# Sheet1.net
KiCad netlist of a schematic drawn in Altium Designer
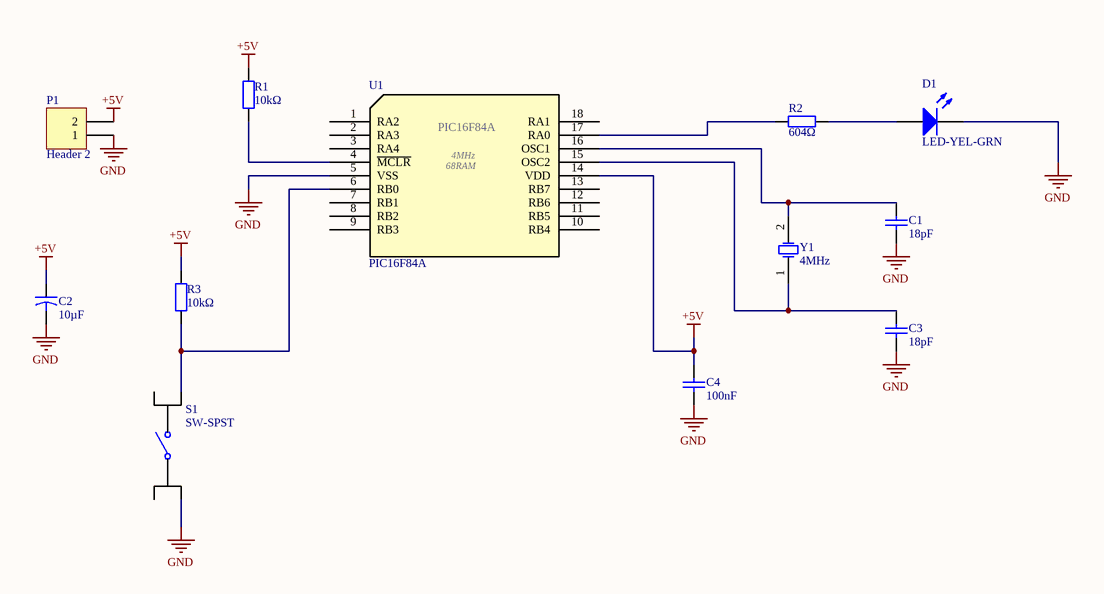
[diagram p0: Sheet1.SchDoc]

(export (version "E")
  (design (tool "Eeschema 10.0.6"))
  (components
    (comp (ref "C1")
      (value "18pF")
      (footprint "capacitor0603nopolar")
      (description "Capacitor")
      (fields (field (name "MANUFACTURER") "WALSIN") (field (name "VOLTAGE") "50V"))
      (libsource (lib "Schlib1") (part "Cap 18pF"))
    )
    (comp (ref "C2")
      (value "Cap 10uF")
      (footprint "cappolar_CM1H106M6L006VR")
      (description "Capacitor")
      (fields
        (field (name "CAPACITY") "10µF")
        (field (name "TOLERANCE") "±20%")
        (field (name "MANUFACTURER") "SAMWHA")
      )
      (libsource (lib "Schlib1") (part "Cap 10uF"))
    )
    (comp (ref "C3")
      (value "18pF")
      (footprint "capacitor0603nopolar")
      (description "Capacitor")
      (fields (field (name "MANUFACTURER") "WALSIN") (field (name "VOLTAGE") "50V"))
      (libsource (lib "Schlib1") (part "Cap 18pF"))
    )
    (comp (ref "C4")
      (value "100nF")
      (footprint "capacitor0603nopolar")
      (description "Capacitor")
      (fields (field (name "MANUFACTURER") "WALSIN") (field (name "VOLTAGE") "100V"))
      (libsource (lib "Schlib1") (part "Cap 100nF"))
    )
    (comp (ref "D1")
      (value "LED-YEL-GRN")
      (footprint "diode0603")
      (description "Typical INFRARED GaAs LED")
      (fields (field (name "MANUFACTURER") "EVERLIGHT") (field (name "VOLTAGE") "1,7...2,4V"))
      (libsource (lib "Schlib1") (part "LED-YEL-GRN"))
    )
    (comp (ref "P1")
      (value "Header 2")
      (footprint "header2,54")
      (description "Header, 2-Pin")
      (fields (field (name "MANUFACTURER") "TE CONNECTIVITY"))
      (libsource (lib "Schlib1") (part "Header 2"))
    )
    (comp (ref "R1")
      (value "10kΩ")
      (footprint "resistor0603")
      (description "Resistor")
      (fields (field (name "MANUFACTURER") "ROYAL OHM") (field (name "TOLERANCE") "±1%"))
      (libsource (lib "Schlib1") (part "Resistor 10Kohm"))
    )
    (comp (ref "R2")
      (value "604Ω")
      (footprint "resistor0603")
      (description "Resistor")
      (fields
        (field (name "MANUFACTURER") "WALSIN")
        (field (name "TOLERANCE") "±1%")
        (field (name "RESISTANCE") "604Ω")
      )
      (libsource (lib "Schlib1") (part "Resistor 604ohm"))
    )
    (comp (ref "R3")
      (value "10kΩ")
      (footprint "resistor0603")
      (description "Resistor")
      (fields (field (name "MANUFACTURER") "ROYAL OHM") (field (name "TOLERANCE") "±1%"))
      (libsource (lib "Schlib1") (part "Resistor 10Kohm"))
    )
    (comp (ref "S1")
      (value "SW-SPST")
      (footprint "switch")
      (description "Single-Pole, Single-Throw Switch")
      (fields (field (name "MANUFACTURER") "NKK SWITCHES"))
      (libsource (lib "Schlib1") (part "SW-SPST"))
    )
    (comp (ref "U1")
      (value "PIC16F84A")
      (footprint "DIP18")
      (description "Microchip")
      (fields (field (name "VOLTAGE") "4...5,5V DC") (field (name "MANUFACTURER") "MICROCHIP TECHNOLOGY"))
      (libsource (lib "Schlib1") (part "PIC16F84A"))
    )
    (comp (ref "Y1")
      (value "4MHz")
      (footprint "oscilator_XTAL003071")
      (description "Crystal Oscillator")
      (fields (field (name "MANUFACTURER") "IQD FREQUENCY PRODUCTS") (field (name "POWER") "0,5mW"))
      (libsource (lib "Schlib1") (part "Oscylator 4MHz"))
    )
  )
  (nets
    (net (code "1") (name "+5V") (class "Default")
      (node (ref "C2") (pin "1") (pinfunction "1_1") (pintype "passive"))
      (node (ref "C4") (pin "2") (pinfunction "2_2") (pintype "passive"))
      (node (ref "P1") (pin "2") (pinfunction "2_2") (pintype "passive"))
      (node (ref "R1") (pin "2") (pinfunction "2_2") (pintype "passive"))
      (node (ref "R3") (pin "2") (pinfunction "2_2") (pintype "passive"))
      (node (ref "U1") (pin "14") (pinfunction "VDD_14") (pintype "passive"))
    )
    (net (code "2") (name "GND") (class "Default")
      (node (ref "C1") (pin "1") (pinfunction "1_1") (pintype "passive"))
      (node (ref "C2") (pin "2") (pinfunction "2_2") (pintype "passive"))
      (node (ref "C3") (pin "1") (pinfunction "1_1") (pintype "passive"))
      (node (ref "C4") (pin "1") (pinfunction "1_1") (pintype "passive"))
      (node (ref "D1") (pin "2") (pinfunction "K_2") (pintype "passive"))
      (node (ref "P1") (pin "1") (pinfunction "1_1") (pintype "passive"))
      (node (ref "S1") (pin "2") (pinfunction "NO_2") (pintype "passive"))
      (node (ref "U1") (pin "5") (pinfunction "VSS_5") (pintype "passive"))
    )
    (net (code "3") (name "Net-(D1-A)") (class "Default")
      (node (ref "D1") (pin "1") (pinfunction "A_1") (pintype "passive"))
      (node (ref "R2") (pin "2") (pinfunction "2_2") (pintype "passive"))
    )
    (net (code "4") (name "Net-(U1-OSC1)") (class "Default")
      (node (ref "C1") (pin "2") (pinfunction "2_2") (pintype "passive"))
      (node (ref "U1") (pin "16") (pinfunction "OSC1_16") (pintype "passive"))
      (node (ref "Y1") (pin "2") (pinfunction "OSC2_2") (pintype "passive"))
    )
    (net (code "5") (name "Net-(U1-OSC2)") (class "Default")
      (node (ref "C3") (pin "2") (pinfunction "2_2") (pintype "passive"))
      (node (ref "U1") (pin "15") (pinfunction "OSC2_15") (pintype "passive"))
      (node (ref "Y1") (pin "1") (pinfunction "OSC1_1") (pintype "passive"))
    )
    (net (code "6") (name "Net-(U1-RA0)") (class "Default")
      (node (ref "R2") (pin "1") (pinfunction "1_1") (pintype "passive"))
      (node (ref "U1") (pin "17") (pinfunction "RA0_17") (pintype "passive"))
    )
    (net (code "7") (name "Net-(U1-RB0)") (class "Default")
      (node (ref "R3") (pin "1") (pinfunction "1_1") (pintype "passive"))
      (node (ref "S1") (pin "4") (pinfunction "NO_4") (pintype "passive"))
      (node (ref "U1") (pin "6") (pinfunction "RB0_6") (pintype "passive"))
    )
    (net (code "8") (name "Net-(U1-~{MCLR})") (class "Default")
      (node (ref "R1") (pin "1") (pinfunction "1_1") (pintype "passive"))
      (node (ref "U1") (pin "4") (pinfunction "~{MCLR}_4") (pintype "passive"))
    )
    (net (code "9") (name "unconnected-(S1-NO-Pad1)") (class "Default")
      (node (ref "S1") (pin "1") (pinfunction "NO_1") (pintype "passive"))
    )
    (net (code "10") (name "unconnected-(S1-NO-Pad3)") (class "Default")
      (node (ref "S1") (pin "3") (pinfunction "NO_3") (pintype "passive"))
    )
    (net (code "11") (name "unconnected-(U1-RA1-Pad18)") (class "Default")
      (node (ref "U1") (pin "18") (pinfunction "RA1_18") (pintype "passive"))
    )
    (net (code "12") (name "unconnected-(U1-RA2-Pad1)") (class "Default")
      (node (ref "U1") (pin "1") (pinfunction "RA2_1") (pintype "passive"))
    )
    (net (code "13") (name "unconnected-(U1-RA3-Pad2)") (class "Default")
      (node (ref "U1") (pin "2") (pinfunction "RA3_2") (pintype "passive"))
    )
    (net (code "14") (name "unconnected-(U1-RA4-Pad3)") (class "Default")
      (node (ref "U1") (pin "3") (pinfunction "RA4_3") (pintype "passive"))
    )
    (net (code "15") (name "unconnected-(U1-RB1-Pad7)") (class "Default")
      (node (ref "U1") (pin "7") (pinfunction "RB1_7") (pintype "passive"))
    )
    (net (code "16") (name "unconnected-(U1-RB2-Pad8)") (class "Default")
      (node (ref "U1") (pin "8") (pinfunction "RB2_8") (pintype "passive"))
    )
    (net (code "17") (name "unconnected-(U1-RB3-Pad9)") (class "Default")
      (node (ref "U1") (pin "9") (pinfunction "RB3_9") (pintype "passive"))
    )
    (net (code "18") (name "unconnected-(U1-RB4-Pad10)") (class "Default")
      (node (ref "U1") (pin "10") (pinfunction "RB4_10") (pintype "passive"))
    )
    (net (code "19") (name "unconnected-(U1-RB5-Pad11)") (class "Default")
      (node (ref "U1") (pin "11") (pinfunction "RB5_11") (pintype "passive"))
    )
    (net (code "20") (name "unconnected-(U1-RB6-Pad12)") (class "Default")
      (node (ref "U1") (pin "12") (pinfunction "RB6_12") (pintype "passive"))
    )
    (net (code "21") (name "unconnected-(U1-RB7-Pad13)") (class "Default")
      (node (ref "U1") (pin "13") (pinfunction "RB7_13") (pintype "passive"))
    )
  )
)
